# Chargeur_Plomb.net
KiCad netlist of a schematic drawn in Altium Designer
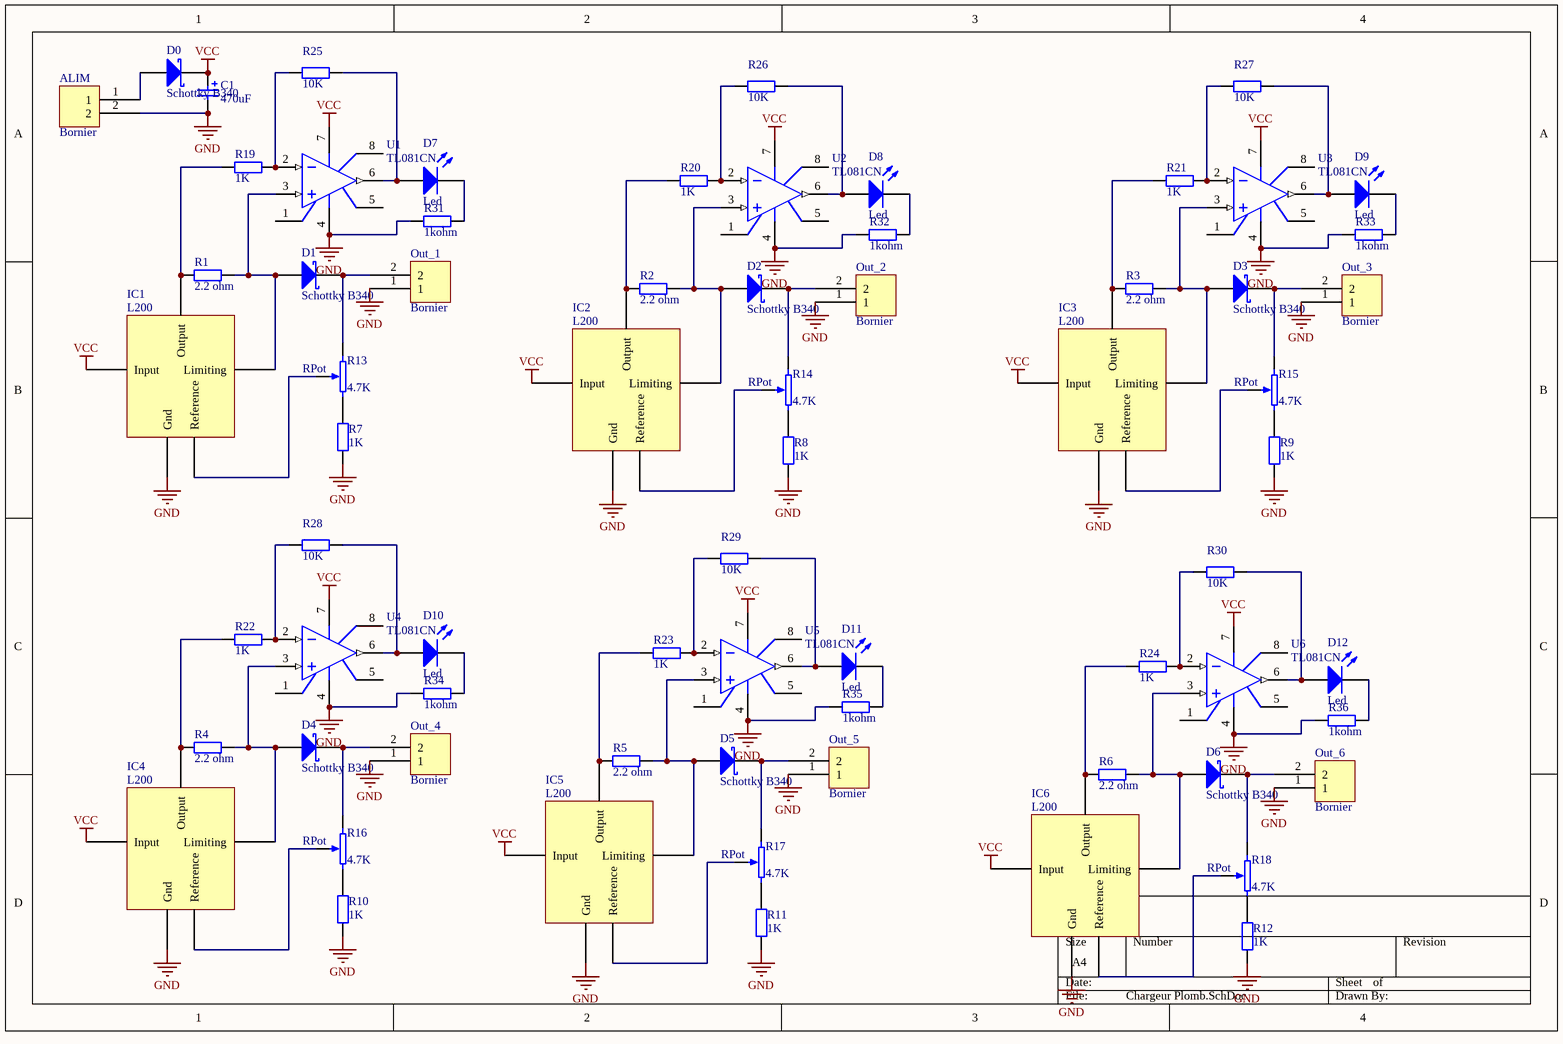
[diagram p0: Chargeur Plomb.SchDoc]

(export (version "E")
  (design (tool "Eeschema 10.0.6"))
  (components
    (comp (ref "ALIM") (value "Bornier") (footprint "Bornier") (libsource (lib "") (part "Bornier2_1")))
    (comp (ref "C1")
      (value "470uF")
      (footprint "Capa_pol1")
      (libsource (lib "lib_Robotronik") (part "Capa Pol"))
    )
    (comp (ref "D0")
      (value "Schottky B340")
      (footprint "SMC")
      (libsource (lib "lib_Robotronik") (part "Schottky B340"))
    )
    (comp (ref "D1")
      (value "Schottky B340")
      (footprint "SMC")
      (libsource (lib "lib_Robotronik") (part "Schottky B340"))
    )
    (comp (ref "D2")
      (value "Schottky B340")
      (footprint "SMC")
      (libsource (lib "lib_Robotronik") (part "Schottky B340"))
    )
    (comp (ref "D3")
      (value "Schottky B340")
      (footprint "SMC")
      (libsource (lib "lib_Robotronik") (part "Schottky B340"))
    )
    (comp (ref "D4")
      (value "Schottky B340")
      (footprint "SMC")
      (libsource (lib "lib_Robotronik") (part "Schottky B340"))
    )
    (comp (ref "D5")
      (value "Schottky B340")
      (footprint "SMC")
      (libsource (lib "lib_Robotronik") (part "Schottky B340"))
    )
    (comp (ref "D6")
      (value "Schottky B340")
      (footprint "SMC")
      (libsource (lib "lib_Robotronik") (part "Schottky B340"))
    )
    (comp (ref "D7")
      (value "Led")
      (footprint "LED")
      (description "LED")
      (fields (field (name "PUBLISHER") "Altium Limited"))
      (libsource (lib "LIBRAIRIE_INTEGREE_PHELMA1") (part "Led"))
    )
    (comp (ref "D8")
      (value "Led")
      (footprint "LED")
      (description "LED")
      (fields (field (name "PUBLISHER") "Altium Limited"))
      (libsource (lib "LIBRAIRIE_INTEGREE_PHELMA1") (part "Led"))
    )
    (comp (ref "D9")
      (value "Led")
      (footprint "LED")
      (description "LED")
      (fields (field (name "PUBLISHER") "Altium Limited"))
      (libsource (lib "LIBRAIRIE_INTEGREE_PHELMA1") (part "Led"))
    )
    (comp (ref "D10")
      (value "Led")
      (footprint "LED")
      (description "LED")
      (fields (field (name "PUBLISHER") "Altium Limited"))
      (libsource (lib "LIBRAIRIE_INTEGREE_PHELMA1") (part "Led"))
    )
    (comp (ref "D11")
      (value "Led")
      (footprint "LED")
      (description "LED")
      (fields (field (name "PUBLISHER") "Altium Limited"))
      (libsource (lib "LIBRAIRIE_INTEGREE_PHELMA1") (part "Led"))
    )
    (comp (ref "D12")
      (value "Led")
      (footprint "LED")
      (description "LED")
      (fields (field (name "PUBLISHER") "Altium Limited"))
      (libsource (lib "LIBRAIRIE_INTEGREE_PHELMA1") (part "Led"))
    )
    (comp (ref "IC1") (value "L200") (footprint "Pentawatt") (libsource (lib "lib_Robotronik") (part "L200")))
    (comp (ref "IC2") (value "L200") (footprint "Pentawatt") (libsource (lib "lib_Robotronik") (part "L200")))
    (comp (ref "IC3") (value "L200") (footprint "Pentawatt") (libsource (lib "lib_Robotronik") (part "L200")))
    (comp (ref "IC4") (value "L200") (footprint "Pentawatt") (libsource (lib "lib_Robotronik") (part "L200")))
    (comp (ref "IC5") (value "L200") (footprint "Pentawatt") (libsource (lib "lib_Robotronik") (part "L200")))
    (comp (ref "IC6") (value "L200") (footprint "Pentawatt") (libsource (lib "lib_Robotronik") (part "L200")))
    (comp (ref "Out_1")
      (value "Bornier")
      (footprint "Bornier")
      (libsource (lib "lib_Robotronik") (part "Bornier2"))
    )
    (comp (ref "Out_2")
      (value "Bornier")
      (footprint "Bornier")
      (libsource (lib "lib_Robotronik") (part "Bornier2"))
    )
    (comp (ref "Out_3")
      (value "Bornier")
      (footprint "Bornier")
      (libsource (lib "lib_Robotronik") (part "Bornier2"))
    )
    (comp (ref "Out_4")
      (value "Bornier")
      (footprint "Bornier")
      (libsource (lib "lib_Robotronik") (part "Bornier2"))
    )
    (comp (ref "Out_5")
      (value "Bornier")
      (footprint "Bornier")
      (libsource (lib "lib_Robotronik") (part "Bornier2"))
    )
    (comp (ref "Out_6")
      (value "Bornier")
      (footprint "Bornier")
      (libsource (lib "lib_Robotronik") (part "Bornier2"))
    )
    (comp (ref "R1")
      (value "2.2 ohm")
      (footprint "traversant 1/4W")
      (libsource (lib "") (part "Resistance_1"))
    )
    (comp (ref "R2")
      (value "2.2 ohm")
      (footprint "traversant 1/4W")
      (libsource (lib "") (part "Resistance_1"))
    )
    (comp (ref "R3")
      (value "2.2 ohm")
      (footprint "traversant 1/4W")
      (libsource (lib "") (part "Resistance_1"))
    )
    (comp (ref "R4")
      (value "2.2 ohm")
      (footprint "traversant 1/4W")
      (libsource (lib "") (part "Resistance_1"))
    )
    (comp (ref "R5")
      (value "2.2 ohm")
      (footprint "traversant 1/4W")
      (libsource (lib "") (part "Resistance_1"))
    )
    (comp (ref "R6")
      (value "2.2 ohm")
      (footprint "traversant 1/4W")
      (libsource (lib "") (part "Resistance_1"))
    )
    (comp (ref "R7")
      (value "1K")
      (footprint "traversant 1/4W")
      (libsource (lib "lib_Robotronik") (part "Resistance"))
    )
    (comp (ref "R8")
      (value "1K")
      (footprint "traversant 1/4W")
      (libsource (lib "lib_Robotronik") (part "Resistance"))
    )
    (comp (ref "R9")
      (value "1K")
      (footprint "traversant 1/4W")
      (libsource (lib "lib_Robotronik") (part "Resistance"))
    )
    (comp (ref "R10")
      (value "1K")
      (footprint "traversant 1/4W")
      (libsource (lib "lib_Robotronik") (part "Resistance"))
    )
    (comp (ref "R11")
      (value "1K")
      (footprint "traversant 1/4W")
      (libsource (lib "lib_Robotronik") (part "Resistance"))
    )
    (comp (ref "R12")
      (value "1K")
      (footprint "traversant 1/4W")
      (libsource (lib "lib_Robotronik") (part "Resistance"))
    )
    (comp (ref "R13")
      (value "RPot")
      (footprint "AJUSTABLE")
      (description "Potentiometer")
      (fields (field (name "ALTIUM_VALUE") "4.7K") (field (name "PUBLISHER") "Altium Limited"))
      (libsource (lib "LIBRAIRIE_INTEGREE_PHELMA1") (part "RPot"))
    )
    (comp (ref "R14")
      (value "RPot")
      (footprint "AJUSTABLE")
      (description "Potentiometer")
      (fields (field (name "ALTIUM_VALUE") "4.7K") (field (name "PUBLISHER") "Altium Limited"))
      (libsource (lib "LIBRAIRIE_INTEGREE_PHELMA1") (part "RPot"))
    )
    (comp (ref "R15")
      (value "RPot")
      (footprint "AJUSTABLE")
      (description "Potentiometer")
      (fields (field (name "ALTIUM_VALUE") "4.7K") (field (name "PUBLISHER") "Altium Limited"))
      (libsource (lib "LIBRAIRIE_INTEGREE_PHELMA1") (part "RPot"))
    )
    (comp (ref "R16")
      (value "RPot")
      (footprint "AJUSTABLE")
      (description "Potentiometer")
      (fields (field (name "ALTIUM_VALUE") "4.7K") (field (name "PUBLISHER") "Altium Limited"))
      (libsource (lib "LIBRAIRIE_INTEGREE_PHELMA1") (part "RPot"))
    )
    (comp (ref "R17")
      (value "RPot")
      (footprint "AJUSTABLE")
      (description "Potentiometer")
      (fields (field (name "ALTIUM_VALUE") "4.7K") (field (name "PUBLISHER") "Altium Limited"))
      (libsource (lib "LIBRAIRIE_INTEGREE_PHELMA1") (part "RPot"))
    )
    (comp (ref "R18")
      (value "RPot")
      (footprint "AJUSTABLE")
      (description "Potentiometer")
      (fields (field (name "ALTIUM_VALUE") "4.7K") (field (name "PUBLISHER") "Altium Limited"))
      (libsource (lib "LIBRAIRIE_INTEGREE_PHELMA1") (part "RPot"))
    )
    (comp (ref "R19") (value "1K") (footprint "traversant 1/4W") (libsource (lib "") (part "Resistance_1")))
    (comp (ref "R20") (value "1K") (footprint "traversant 1/4W") (libsource (lib "") (part "Resistance_1")))
    (comp (ref "R21") (value "1K") (footprint "traversant 1/4W") (libsource (lib "") (part "Resistance_1")))
    (comp (ref "R22") (value "1K") (footprint "traversant 1/4W") (libsource (lib "") (part "Resistance_1")))
    (comp (ref "R23") (value "1K") (footprint "traversant 1/4W") (libsource (lib "") (part "Resistance_1")))
    (comp (ref "R24") (value "1K") (footprint "traversant 1/4W") (libsource (lib "") (part "Resistance_1")))
    (comp (ref "R25") (value "10K") (footprint "traversant 1/4W") (libsource (lib "") (part "Resistance_1")))
    (comp (ref "R26") (value "10K") (footprint "traversant 1/4W") (libsource (lib "") (part "Resistance_1")))
    (comp (ref "R27") (value "10K") (footprint "traversant 1/4W") (libsource (lib "") (part "Resistance_1")))
    (comp (ref "R28") (value "10K") (footprint "traversant 1/4W") (libsource (lib "") (part "Resistance_1")))
    (comp (ref "R29") (value "10K") (footprint "traversant 1/4W") (libsource (lib "") (part "Resistance_1")))
    (comp (ref "R30") (value "10K") (footprint "traversant 1/4W") (libsource (lib "") (part "Resistance_1")))
    (comp (ref "R31")
      (value "1kohm")
      (footprint "traversant 1/4W")
      (libsource (lib "") (part "Resistance_2"))
    )
    (comp (ref "R32")
      (value "1kohm")
      (footprint "traversant 1/4W")
      (libsource (lib "") (part "Resistance_2"))
    )
    (comp (ref "R33")
      (value "1kohm")
      (footprint "traversant 1/4W")
      (libsource (lib "") (part "Resistance_2"))
    )
    (comp (ref "R34")
      (value "1kohm")
      (footprint "traversant 1/4W")
      (libsource (lib "") (part "Resistance_2"))
    )
    (comp (ref "R35")
      (value "1kohm")
      (footprint "traversant 1/4W")
      (libsource (lib "") (part "Resistance_2"))
    )
    (comp (ref "R36")
      (value "1kohm")
      (footprint "traversant 1/4W")
      (libsource (lib "") (part "Resistance_2"))
    )
    (comp (ref "U1")
      (value "TL081CN")
      (footprint "DIP8")
      (description "General-Purpose J-FET Single Operational Amplifier")
      (fields (field (name "PUBLISHER") "Altium Limited"))
      (libsource (lib "LIBRAIRIE_INTEGREE_PHELMA1") (part "TL081CN"))
    )
    (comp (ref "U2")
      (value "TL081CN")
      (footprint "DIP8")
      (description "General-Purpose J-FET Single Operational Amplifier")
      (fields (field (name "PUBLISHER") "Altium Limited"))
      (libsource (lib "LIBRAIRIE_INTEGREE_PHELMA1") (part "TL081CN"))
    )
    (comp (ref "U3")
      (value "TL081CN")
      (footprint "DIP8")
      (description "General-Purpose J-FET Single Operational Amplifier")
      (fields (field (name "PUBLISHER") "Altium Limited"))
      (libsource (lib "LIBRAIRIE_INTEGREE_PHELMA1") (part "TL081CN"))
    )
    (comp (ref "U4")
      (value "TL081CN")
      (footprint "DIP8")
      (description "General-Purpose J-FET Single Operational Amplifier")
      (fields (field (name "PUBLISHER") "Altium Limited"))
      (libsource (lib "LIBRAIRIE_INTEGREE_PHELMA1") (part "TL081CN"))
    )
    (comp (ref "U5")
      (value "TL081CN")
      (footprint "DIP8")
      (description "General-Purpose J-FET Single Operational Amplifier")
      (fields (field (name "PUBLISHER") "Altium Limited"))
      (libsource (lib "LIBRAIRIE_INTEGREE_PHELMA1") (part "TL081CN"))
    )
    (comp (ref "U6")
      (value "TL081CN")
      (footprint "DIP8")
      (description "General-Purpose J-FET Single Operational Amplifier")
      (fields (field (name "PUBLISHER") "Altium Limited"))
      (libsource (lib "LIBRAIRIE_INTEGREE_PHELMA1") (part "TL081CN"))
    )
  )
  (nets
    (net (code "1") (name "GND") (class "Default")
      (node (ref "ALIM") (pin "2") (pinfunction "2_2") (pintype "passive"))
      (node (ref "C1") (pin "2") (pinfunction "2_2") (pintype "passive"))
      (node (ref "IC1") (pin "3") (pinfunction "Gnd_3") (pintype "passive"))
      (node (ref "IC2") (pin "3") (pinfunction "Gnd_3") (pintype "passive"))
      (node (ref "IC3") (pin "3") (pinfunction "Gnd_3") (pintype "passive"))
      (node (ref "IC4") (pin "3") (pinfunction "Gnd_3") (pintype "passive"))
      (node (ref "IC5") (pin "3") (pinfunction "Gnd_3") (pintype "passive"))
      (node (ref "IC6") (pin "3") (pinfunction "Gnd_3") (pintype "passive"))
      (node (ref "Out_1") (pin "1") (pinfunction "1_1") (pintype "passive"))
      (node (ref "Out_2") (pin "1") (pinfunction "1_1") (pintype "passive"))
      (node (ref "Out_3") (pin "1") (pinfunction "1_1") (pintype "passive"))
      (node (ref "Out_4") (pin "1") (pinfunction "1_1") (pintype "passive"))
      (node (ref "Out_5") (pin "1") (pinfunction "1_1") (pintype "passive"))
      (node (ref "Out_6") (pin "1") (pinfunction "1_1") (pintype "passive"))
      (node (ref "R10") (pin "1") (pinfunction "1_1") (pintype "passive"))
      (node (ref "R11") (pin "1") (pinfunction "1_1") (pintype "passive"))
      (node (ref "R12") (pin "1") (pinfunction "1_1") (pintype "passive"))
      (node (ref "R31") (pin "1") (pinfunction "1_1") (pintype "passive"))
      (node (ref "R32") (pin "1") (pinfunction "1_1") (pintype "passive"))
      (node (ref "R33") (pin "1") (pinfunction "1_1") (pintype "passive"))
      (node (ref "R34") (pin "1") (pinfunction "1_1") (pintype "passive"))
      (node (ref "R35") (pin "1") (pinfunction "1_1") (pintype "passive"))
      (node (ref "R36") (pin "1") (pinfunction "1_1") (pintype "passive"))
      (node (ref "R7") (pin "1") (pinfunction "1_1") (pintype "passive"))
      (node (ref "R8") (pin "1") (pinfunction "1_1") (pintype "passive"))
      (node (ref "R9") (pin "1") (pinfunction "1_1") (pintype "passive"))
      (node (ref "U1") (pin "4") (pinfunction "V-_4") (pintype "power_in"))
      (node (ref "U2") (pin "4") (pinfunction "V-_4") (pintype "power_in"))
      (node (ref "U3") (pin "4") (pinfunction "V-_4") (pintype "power_in"))
      (node (ref "U4") (pin "4") (pinfunction "V-_4") (pintype "power_in"))
      (node (ref "U5") (pin "4") (pinfunction "V-_4") (pintype "power_in"))
      (node (ref "U6") (pin "4") (pinfunction "V-_4") (pintype "power_in"))
    )
    (net (code "2") (name "Net-(D0-A)") (class "Default")
      (node (ref "ALIM") (pin "1") (pinfunction "1_1") (pintype "passive"))
      (node (ref "D0") (pin "1") (pinfunction "A_1") (pintype "passive"))
    )
    (net (code "3") (name "Net-(D1-A)") (class "Default")
      (node (ref "D1") (pin "1") (pinfunction "A_1") (pintype "passive"))
      (node (ref "IC1") (pin "2") (pinfunction "Limiting_2") (pintype "passive"))
      (node (ref "R1") (pin "1") (pinfunction "1_1") (pintype "passive"))
      (node (ref "U1") (pin "3") (pinfunction "IN+_3") (pintype "input"))
    )
    (net (code "4") (name "Net-(D1-K)") (class "Default")
      (node (ref "D1") (pin "2") (pinfunction "K_2") (pintype "passive"))
      (node (ref "Out_1") (pin "2") (pinfunction "2_2") (pintype "passive"))
      (node (ref "R13") (pin "3") (pinfunction "TOP_3") (pintype "passive"))
    )
    (net (code "5") (name "Net-(D2-A)") (class "Default")
      (node (ref "D2") (pin "1") (pinfunction "A_1") (pintype "passive"))
      (node (ref "IC2") (pin "2") (pinfunction "Limiting_2") (pintype "passive"))
      (node (ref "R2") (pin "1") (pinfunction "1_1") (pintype "passive"))
      (node (ref "U2") (pin "3") (pinfunction "IN+_3") (pintype "input"))
    )
    (net (code "6") (name "Net-(D2-K)") (class "Default")
      (node (ref "D2") (pin "2") (pinfunction "K_2") (pintype "passive"))
      (node (ref "Out_2") (pin "2") (pinfunction "2_2") (pintype "passive"))
      (node (ref "R14") (pin "3") (pinfunction "TOP_3") (pintype "passive"))
    )
    (net (code "7") (name "Net-(D3-A)") (class "Default")
      (node (ref "D3") (pin "1") (pinfunction "A_1") (pintype "passive"))
      (node (ref "IC3") (pin "2") (pinfunction "Limiting_2") (pintype "passive"))
      (node (ref "R3") (pin "1") (pinfunction "1_1") (pintype "passive"))
      (node (ref "U3") (pin "3") (pinfunction "IN+_3") (pintype "input"))
    )
    (net (code "8") (name "Net-(D3-K)") (class "Default")
      (node (ref "D3") (pin "2") (pinfunction "K_2") (pintype "passive"))
      (node (ref "Out_3") (pin "2") (pinfunction "2_2") (pintype "passive"))
      (node (ref "R15") (pin "3") (pinfunction "TOP_3") (pintype "passive"))
    )
    (net (code "9") (name "Net-(D4-A)") (class "Default")
      (node (ref "D4") (pin "1") (pinfunction "A_1") (pintype "passive"))
      (node (ref "IC4") (pin "2") (pinfunction "Limiting_2") (pintype "passive"))
      (node (ref "R4") (pin "1") (pinfunction "1_1") (pintype "passive"))
      (node (ref "U4") (pin "3") (pinfunction "IN+_3") (pintype "input"))
    )
    (net (code "10") (name "Net-(D4-K)") (class "Default")
      (node (ref "D4") (pin "2") (pinfunction "K_2") (pintype "passive"))
      (node (ref "Out_4") (pin "2") (pinfunction "2_2") (pintype "passive"))
      (node (ref "R16") (pin "3") (pinfunction "TOP_3") (pintype "passive"))
    )
    (net (code "11") (name "Net-(D5-A)") (class "Default")
      (node (ref "D5") (pin "1") (pinfunction "A_1") (pintype "passive"))
      (node (ref "IC5") (pin "2") (pinfunction "Limiting_2") (pintype "passive"))
      (node (ref "R5") (pin "1") (pinfunction "1_1") (pintype "passive"))
      (node (ref "U5") (pin "3") (pinfunction "IN+_3") (pintype "input"))
    )
    (net (code "12") (name "Net-(D5-K)") (class "Default")
      (node (ref "D5") (pin "2") (pinfunction "K_2") (pintype "passive"))
      (node (ref "Out_5") (pin "2") (pinfunction "2_2") (pintype "passive"))
      (node (ref "R17") (pin "3") (pinfunction "TOP_3") (pintype "passive"))
    )
    (net (code "13") (name "Net-(D6-A)") (class "Default")
      (node (ref "D6") (pin "1") (pinfunction "A_1") (pintype "passive"))
      (node (ref "IC6") (pin "2") (pinfunction "Limiting_2") (pintype "passive"))
      (node (ref "R6") (pin "1") (pinfunction "1_1") (pintype "passive"))
      (node (ref "U6") (pin "3") (pinfunction "IN+_3") (pintype "input"))
    )
    (net (code "14") (name "Net-(D6-K)") (class "Default")
      (node (ref "D6") (pin "2") (pinfunction "K_2") (pintype "passive"))
      (node (ref "Out_6") (pin "2") (pinfunction "2_2") (pintype "passive"))
      (node (ref "R18") (pin "3") (pinfunction "TOP_3") (pintype "passive"))
    )
    (net (code "15") (name "Net-(D7-A)") (class "Default")
      (node (ref "D7") (pin "1") (pinfunction "A_1") (pintype "passive"))
      (node (ref "R25") (pin "1") (pinfunction "1_1") (pintype "passive"))
      (node (ref "U1") (pin "6") (pinfunction "OUT_6") (pintype "output"))
    )
    (net (code "16") (name "Net-(D7-K)") (class "Default")
      (node (ref "D7") (pin "2") (pinfunction "K_2") (pintype "passive"))
      (node (ref "R31") (pin "2") (pinfunction "2_2") (pintype "passive"))
    )
    (net (code "17") (name "Net-(D8-A)") (class "Default")
      (node (ref "D8") (pin "1") (pinfunction "A_1") (pintype "passive"))
      (node (ref "R26") (pin "1") (pinfunction "1_1") (pintype "passive"))
      (node (ref "U2") (pin "6") (pinfunction "OUT_6") (pintype "output"))
    )
    (net (code "18") (name "Net-(D8-K)") (class "Default")
      (node (ref "D8") (pin "2") (pinfunction "K_2") (pintype "passive"))
      (node (ref "R32") (pin "2") (pinfunction "2_2") (pintype "passive"))
    )
    (net (code "19") (name "Net-(D9-A)") (class "Default")
      (node (ref "D9") (pin "1") (pinfunction "A_1") (pintype "passive"))
      (node (ref "R27") (pin "1") (pinfunction "1_1") (pintype "passive"))
      (node (ref "U3") (pin "6") (pinfunction "OUT_6") (pintype "output"))
    )
    (net (code "20") (name "Net-(D9-K)") (class "Default")
      (node (ref "D9") (pin "2") (pinfunction "K_2") (pintype "passive"))
      (node (ref "R33") (pin "2") (pinfunction "2_2") (pintype "passive"))
    )
    (net (code "21") (name "Net-(D10-A)") (class "Default")
      (node (ref "D10") (pin "1") (pinfunction "A_1") (pintype "passive"))
      (node (ref "R28") (pin "1") (pinfunction "1_1") (pintype "passive"))
      (node (ref "U4") (pin "6") (pinfunction "OUT_6") (pintype "output"))
    )
    (net (code "22") (name "Net-(D10-K)") (class "Default")
      (node (ref "D10") (pin "2") (pinfunction "K_2") (pintype "passive"))
      (node (ref "R34") (pin "2") (pinfunction "2_2") (pintype "passive"))
    )
    (net (code "23") (name "Net-(D11-A)") (class "Default")
      (node (ref "D11") (pin "1") (pinfunction "A_1") (pintype "passive"))
      (node (ref "R29") (pin "1") (pinfunction "1_1") (pintype "passive"))
      (node (ref "U5") (pin "6") (pinfunction "OUT_6") (pintype "output"))
    )
    (net (code "24") (name "Net-(D11-K)") (class "Default")
      (node (ref "D11") (pin "2") (pinfunction "K_2") (pintype "passive"))
      (node (ref "R35") (pin "2") (pinfunction "2_2") (pintype "passive"))
    )
    (net (code "25") (name "Net-(D12-A)") (class "Default")
      (node (ref "D12") (pin "1") (pinfunction "A_1") (pintype "passive"))
      (node (ref "R30") (pin "1") (pinfunction "1_1") (pintype "passive"))
      (node (ref "U6") (pin "6") (pinfunction "OUT_6") (pintype "output"))
    )
    (net (code "26") (name "Net-(D12-K)") (class "Default")
      (node (ref "D12") (pin "2") (pinfunction "K_2") (pintype "passive"))
      (node (ref "R36") (pin "2") (pinfunction "2_2") (pintype "passive"))
    )
    (net (code "27") (name "Net-(IC1-Output)") (class "Default")
      (node (ref "IC1") (pin "5") (pinfunction "Output_5") (pintype "passive"))
      (node (ref "R1") (pin "2") (pinfunction "2_2") (pintype "passive"))
      (node (ref "R19") (pin "2") (pinfunction "2_2") (pintype "passive"))
    )
    (net (code "28") (name "Net-(IC1-Reference)") (class "Default")
      (node (ref "IC1") (pin "4") (pinfunction "Reference_4") (pintype "passive"))
      (node (ref "R13") (pin "2") (pinfunction "TAP_2") (pintype "passive"))
    )
    (net (code "29") (name "Net-(IC2-Output)") (class "Default")
      (node (ref "IC2") (pin "5") (pinfunction "Output_5") (pintype "passive"))
      (node (ref "R2") (pin "2") (pinfunction "2_2") (pintype "passive"))
      (node (ref "R20") (pin "2") (pinfunction "2_2") (pintype "passive"))
    )
    (net (code "30") (name "Net-(IC2-Reference)") (class "Default")
      (node (ref "IC2") (pin "4") (pinfunction "Reference_4") (pintype "passive"))
      (node (ref "R14") (pin "2") (pinfunction "TAP_2") (pintype "passive"))
    )
    (net (code "31") (name "Net-(IC3-Output)") (class "Default")
      (node (ref "IC3") (pin "5") (pinfunction "Output_5") (pintype "passive"))
      (node (ref "R21") (pin "2") (pinfunction "2_2") (pintype "passive"))
      (node (ref "R3") (pin "2") (pinfunction "2_2") (pintype "passive"))
    )
    (net (code "32") (name "Net-(IC3-Reference)") (class "Default")
      (node (ref "IC3") (pin "4") (pinfunction "Reference_4") (pintype "passive"))
      (node (ref "R15") (pin "2") (pinfunction "TAP_2") (pintype "passive"))
    )
    (net (code "33") (name "Net-(IC4-Output)") (class "Default")
      (node (ref "IC4") (pin "5") (pinfunction "Output_5") (pintype "passive"))
      (node (ref "R22") (pin "2") (pinfunction "2_2") (pintype "passive"))
      (node (ref "R4") (pin "2") (pinfunction "2_2") (pintype "passive"))
    )
    (net (code "34") (name "Net-(IC4-Reference)") (class "Default")
      (node (ref "IC4") (pin "4") (pinfunction "Reference_4") (pintype "passive"))
      (node (ref "R16") (pin "2") (pinfunction "TAP_2") (pintype "passive"))
    )
    (net (code "35") (name "Net-(IC5-Output)") (class "Default")
      (node (ref "IC5") (pin "5") (pinfunction "Output_5") (pintype "passive"))
      (node (ref "R23") (pin "2") (pinfunction "2_2") (pintype "passive"))
      (node (ref "R5") (pin "2") (pinfunction "2_2") (pintype "passive"))
    )
    (net (code "36") (name "Net-(IC5-Reference)") (class "Default")
      (node (ref "IC5") (pin "4") (pinfunction "Reference_4") (pintype "passive"))
      (node (ref "R17") (pin "2") (pinfunction "TAP_2") (pintype "passive"))
    )
    (net (code "37") (name "Net-(IC6-Output)") (class "Default")
      (node (ref "IC6") (pin "5") (pinfunction "Output_5") (pintype "passive"))
      (node (ref "R24") (pin "2") (pinfunction "2_2") (pintype "passive"))
      (node (ref "R6") (pin "2") (pinfunction "2_2") (pintype "passive"))
    )
    (net (code "38") (name "Net-(IC6-Reference)") (class "Default")
      (node (ref "IC6") (pin "4") (pinfunction "Reference_4") (pintype "passive"))
      (node (ref "R18") (pin "2") (pinfunction "TAP_2") (pintype "passive"))
    )
    (net (code "39") (name "Net-(R13-BOT)") (class "Default")
      (node (ref "R13") (pin "1") (pinfunction "BOT_1") (pintype "passive"))
      (node (ref "R7") (pin "2") (pinfunction "2_2") (pintype "passive"))
    )
    (net (code "40") (name "Net-(R14-BOT)") (class "Default")
      (node (ref "R14") (pin "1") (pinfunction "BOT_1") (pintype "passive"))
      (node (ref "R8") (pin "2") (pinfunction "2_2") (pintype "passive"))
    )
    (net (code "41") (name "Net-(R15-BOT)") (class "Default")
      (node (ref "R15") (pin "1") (pinfunction "BOT_1") (pintype "passive"))
      (node (ref "R9") (pin "2") (pinfunction "2_2") (pintype "passive"))
    )
    (net (code "42") (name "Net-(R16-BOT)") (class "Default")
      (node (ref "R10") (pin "2") (pinfunction "2_2") (pintype "passive"))
      (node (ref "R16") (pin "1") (pinfunction "BOT_1") (pintype "passive"))
    )
    (net (code "43") (name "Net-(R17-BOT)") (class "Default")
      (node (ref "R11") (pin "2") (pinfunction "2_2") (pintype "passive"))
      (node (ref "R17") (pin "1") (pinfunction "BOT_1") (pintype "passive"))
    )
    (net (code "44") (name "Net-(R18-BOT)") (class "Default")
      (node (ref "R12") (pin "2") (pinfunction "2_2") (pintype "passive"))
      (node (ref "R18") (pin "1") (pinfunction "BOT_1") (pintype "passive"))
    )
    (net (code "45") (name "Net-(U1-IN-)") (class "Default")
      (node (ref "R19") (pin "1") (pinfunction "1_1") (pintype "passive"))
      (node (ref "R25") (pin "2") (pinfunction "2_2") (pintype "passive"))
      (node (ref "U1") (pin "2") (pinfunction "IN-_2") (pintype "input"))
    )
    (net (code "46") (name "Net-(U2-IN-)") (class "Default")
      (node (ref "R20") (pin "1") (pinfunction "1_1") (pintype "passive"))
      (node (ref "R26") (pin "2") (pinfunction "2_2") (pintype "passive"))
      (node (ref "U2") (pin "2") (pinfunction "IN-_2") (pintype "input"))
    )
    (net (code "47") (name "Net-(U3-IN-)") (class "Default")
      (node (ref "R21") (pin "1") (pinfunction "1_1") (pintype "passive"))
      (node (ref "R27") (pin "2") (pinfunction "2_2") (pintype "passive"))
      (node (ref "U3") (pin "2") (pinfunction "IN-_2") (pintype "input"))
    )
    (net (code "48") (name "Net-(U4-IN-)") (class "Default")
      (node (ref "R22") (pin "1") (pinfunction "1_1") (pintype "passive"))
      (node (ref "R28") (pin "2") (pinfunction "2_2") (pintype "passive"))
      (node (ref "U4") (pin "2") (pinfunction "IN-_2") (pintype "input"))
    )
    (net (code "49") (name "Net-(U5-IN-)") (class "Default")
      (node (ref "R23") (pin "1") (pinfunction "1_1") (pintype "passive"))
      (node (ref "R29") (pin "2") (pinfunction "2_2") (pintype "passive"))
      (node (ref "U5") (pin "2") (pinfunction "IN-_2") (pintype "input"))
    )
    (net (code "50") (name "Net-(U6-IN-)") (class "Default")
      (node (ref "R24") (pin "1") (pinfunction "1_1") (pintype "passive"))
      (node (ref "R30") (pin "2") (pinfunction "2_2") (pintype "passive"))
      (node (ref "U6") (pin "2") (pinfunction "IN-_2") (pintype "input"))
    )
    (net (code "51") (name "VCC") (class "Default")
      (node (ref "C1") (pin "1") (pinfunction "1_1") (pintype "passive"))
      (node (ref "D0") (pin "2") (pinfunction "K_2") (pintype "passive"))
      (node (ref "IC1") (pin "1") (pinfunction "Input_1") (pintype "passive"))
      (node (ref "IC2") (pin "1") (pinfunction "Input_1") (pintype "passive"))
      (node (ref "IC3") (pin "1") (pinfunction "Input_1") (pintype "passive"))
      (node (ref "IC4") (pin "1") (pinfunction "Input_1") (pintype "passive"))
      (node (ref "IC5") (pin "1") (pinfunction "Input_1") (pintype "passive"))
      (node (ref "IC6") (pin "1") (pinfunction "Input_1") (pintype "passive"))
      (node (ref "U1") (pin "7") (pinfunction "V+_7") (pintype "power_in"))
      (node (ref "U2") (pin "7") (pinfunction "V+_7") (pintype "power_in"))
      (node (ref "U3") (pin "7") (pinfunction "V+_7") (pintype "power_in"))
      (node (ref "U4") (pin "7") (pinfunction "V+_7") (pintype "power_in"))
      (node (ref "U5") (pin "7") (pinfunction "V+_7") (pintype "power_in"))
      (node (ref "U6") (pin "7") (pinfunction "V+_7") (pintype "power_in"))
    )
    (net (code "52") (name "unconnected-(U1-NC-Pad8)") (class "Default")
      (node (ref "U1") (pin "8") (pinfunction "NC_8") (pintype "passive"))
    )
    (net (code "53") (name "unconnected-(U1-OS_NULL-Pad1)") (class "Default")
      (node (ref "U1") (pin "1") (pinfunction "OS_NULL_1") (pintype "passive"))
    )
    (net (code "54") (name "unconnected-(U1-OS_NULL-Pad5)") (class "Default")
      (node (ref "U1") (pin "5") (pinfunction "OS_NULL_5") (pintype "passive"))
    )
    (net (code "55") (name "unconnected-(U2-NC-Pad8)") (class "Default")
      (node (ref "U2") (pin "8") (pinfunction "NC_8") (pintype "passive"))
    )
    (net (code "56") (name "unconnected-(U2-OS_NULL-Pad1)") (class "Default")
      (node (ref "U2") (pin "1") (pinfunction "OS_NULL_1") (pintype "passive"))
    )
    (net (code "57") (name "unconnected-(U2-OS_NULL-Pad5)") (class "Default")
      (node (ref "U2") (pin "5") (pinfunction "OS_NULL_5") (pintype "passive"))
    )
    (net (code "58") (name "unconnected-(U3-NC-Pad8)") (class "Default")
      (node (ref "U3") (pin "8") (pinfunction "NC_8") (pintype "passive"))
    )
    (net (code "59") (name "unconnected-(U3-OS_NULL-Pad1)") (class "Default")
      (node (ref "U3") (pin "1") (pinfunction "OS_NULL_1") (pintype "passive"))
    )
    (net (code "60") (name "unconnected-(U3-OS_NULL-Pad5)") (class "Default")
      (node (ref "U3") (pin "5") (pinfunction "OS_NULL_5") (pintype "passive"))
    )
    (net (code "61") (name "unconnected-(U4-NC-Pad8)") (class "Default")
      (node (ref "U4") (pin "8") (pinfunction "NC_8") (pintype "passive"))
    )
    (net (code "62") (name "unconnected-(U4-OS_NULL-Pad1)") (class "Default")
      (node (ref "U4") (pin "1") (pinfunction "OS_NULL_1") (pintype "passive"))
    )
    (net (code "63") (name "unconnected-(U4-OS_NULL-Pad5)") (class "Default")
      (node (ref "U4") (pin "5") (pinfunction "OS_NULL_5") (pintype "passive"))
    )
    (net (code "64") (name "unconnected-(U5-NC-Pad8)") (class "Default")
      (node (ref "U5") (pin "8") (pinfunction "NC_8") (pintype "passive"))
    )
    (net (code "65") (name "unconnected-(U5-OS_NULL-Pad1)") (class "Default")
      (node (ref "U5") (pin "1") (pinfunction "OS_NULL_1") (pintype "passive"))
    )
    (net (code "66") (name "unconnected-(U5-OS_NULL-Pad5)") (class "Default")
      (node (ref "U5") (pin "5") (pinfunction "OS_NULL_5") (pintype "passive"))
    )
    (net (code "67") (name "unconnected-(U6-NC-Pad8)") (class "Default")
      (node (ref "U6") (pin "8") (pinfunction "NC_8") (pintype "passive"))
    )
    (net (code "68") (name "unconnected-(U6-OS_NULL-Pad1)") (class "Default")
      (node (ref "U6") (pin "1") (pinfunction "OS_NULL_1") (pintype "passive"))
    )
    (net (code "69") (name "unconnected-(U6-OS_NULL-Pad5)") (class "Default")
      (node (ref "U6") (pin "5") (pinfunction "OS_NULL_5") (pintype "passive"))
    )
  )
)
